# HWProgUSB.net
KiCad netlist of a schematic drawn in EAGLE
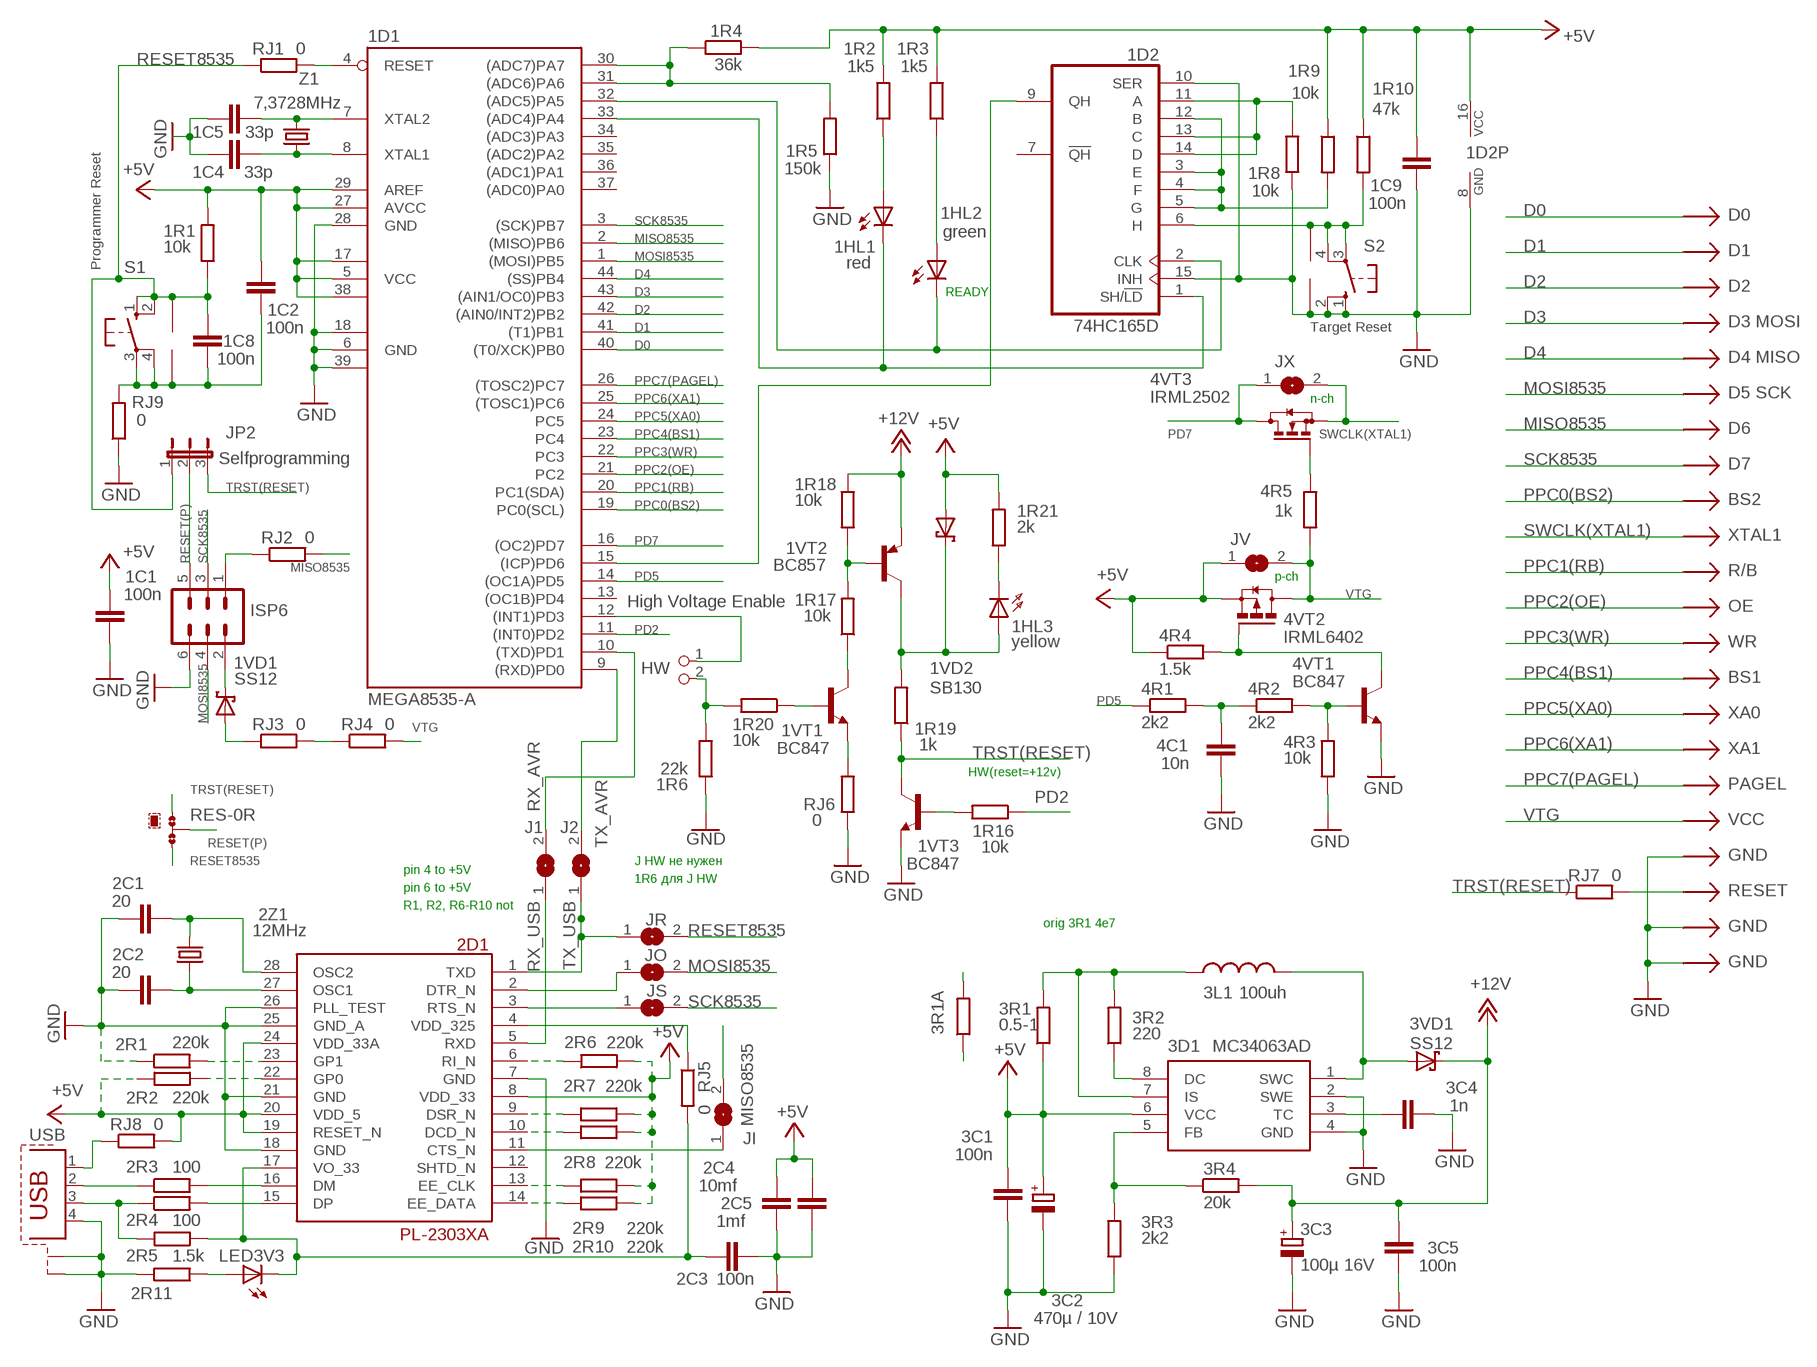
[diagram p0: schematic, sheet 1]

(export (version "E")
  (design (tool "Eeschema 10.0.6"))
  (components
    (comp (ref "1C1")
      (value "100n")
      (footprint "eagle-import:C0805")
      (libsource (lib "eagle-import") (part "rcl_C-EUC0805"))
    )
    (comp (ref "1C2")
      (value "100n")
      (footprint "eagle-import:C0805")
      (libsource (lib "eagle-import") (part "rcl_C-EUC0805"))
    )
    (comp (ref "1C4")
      (value "33p")
      (footprint "eagle-import:C0805")
      (libsource (lib "eagle-import") (part "rcl_C-EUC0805"))
    )
    (comp (ref "1C5")
      (value "33p")
      (footprint "eagle-import:C0805")
      (libsource (lib "eagle-import") (part "rcl_C-EUC0805"))
    )
    (comp (ref "1C8")
      (value "100n")
      (footprint "eagle-import:C0805")
      (libsource (lib "eagle-import") (part "rcl_C-EUC0805"))
    )
    (comp (ref "1C9")
      (value "100n")
      (footprint "eagle-import:C0805")
      (libsource (lib "eagle-import") (part "rcl_C-EUC0805"))
    )
    (comp (ref "1D1")
      (value "MEGA8535-A")
      (footprint "eagle-import:TQFP44")
      (fields (field (name "MPN") "ATMEGA8535-16AU"))
      (libsource (lib "eagle-import") (part "MEGA8535-A"))
    )
    (comp (ref "1D2")
      (value "74HC165D")
      (footprint "eagle-import:SO16")
      (libsource (lib "eagle-import") (part "74165DHC"))
    )
    (comp (ref "1HL1")
      (value "red")
      (footprint "eagle-import:LED5MM")
      (libsource (lib "eagle-import") (part "LED5MM"))
    )
    (comp (ref "1HL2")
      (value "green")
      (footprint "eagle-import:LED5MM")
      (libsource (lib "eagle-import") (part "LED5MM"))
    )
    (comp (ref "1HL3")
      (value "yellow")
      (footprint "eagle-import:LED5MM")
      (libsource (lib "eagle-import") (part "rc-elektronik_LED5MM"))
    )
    (comp (ref "1R1")
      (value "10k")
      (footprint "eagle-import:M0805")
      (libsource (lib "eagle-import") (part "R-EU_M0805"))
    )
    (comp (ref "1R2")
      (value "1k5")
      (footprint "eagle-import:M0805")
      (libsource (lib "eagle-import") (part "R-EU_M0805"))
    )
    (comp (ref "1R3")
      (value "1k5")
      (footprint "eagle-import:M0805")
      (libsource (lib "eagle-import") (part "R-EU_M0805"))
    )
    (comp (ref "1R4")
      (value "36k")
      (footprint "eagle-import:M0805")
      (libsource (lib "eagle-import") (part "R-EU_M0805"))
    )
    (comp (ref "1R5")
      (value "150k")
      (footprint "eagle-import:R1206")
      (libsource (lib "eagle-import") (part "R-EU_R1206"))
    )
    (comp (ref "1R6")
      (value "22k")
      (footprint "eagle-import:M1206")
      (libsource (lib "eagle-import") (part "R-EU_M1206"))
    )
    (comp (ref "1R8")
      (value "10k")
      (footprint "eagle-import:M0805")
      (libsource (lib "eagle-import") (part "R-EU_M0805"))
    )
    (comp (ref "1R9")
      (value "10k")
      (footprint "eagle-import:M0805")
      (libsource (lib "eagle-import") (part "R-EU_M0805"))
    )
    (comp (ref "1R10")
      (value "47k")
      (footprint "eagle-import:M0805")
      (libsource (lib "eagle-import") (part "R-EU_M0805"))
    )
    (comp (ref "1R16")
      (value "10k")
      (footprint "eagle-import:R0805")
      (libsource (lib "eagle-import") (part "R-EU_R0805"))
    )
    (comp (ref "1R17")
      (value "10k")
      (footprint "eagle-import:M0805")
      (libsource (lib "eagle-import") (part "R-EU_M0805"))
    )
    (comp (ref "1R18")
      (value "10k")
      (footprint "eagle-import:M0805")
      (libsource (lib "eagle-import") (part "R-EU_M0805"))
    )
    (comp (ref "1R19")
      (value "1k")
      (footprint "eagle-import:M0805")
      (libsource (lib "eagle-import") (part "R-EU_M0805"))
    )
    (comp (ref "1R20")
      (value "10k")
      (footprint "eagle-import:M0805")
      (libsource (lib "eagle-import") (part "R-EU_M0805"))
    )
    (comp (ref "1R21")
      (value "2k")
      (footprint "eagle-import:R1206W")
      (libsource (lib "eagle-import") (part "R-EU_R1206W"))
    )
    (comp (ref "1VD1")
      (value "SS12")
      (footprint "eagle-import:SMB")
      (libsource (lib "eagle-import") (part "SCHOTTKY-DIODESMD"))
    )
    (comp (ref "1VD2")
      (value "SB130")
      (footprint "eagle-import:SMB")
      (libsource (lib "eagle-import") (part "SCHOTTKY-DIODESMD"))
    )
    (comp (ref "1VT1")
      (value "BC847")
      (footprint "eagle-import:SOT23")
      (libsource (lib "eagle-import") (part "BC847"))
    )
    (comp (ref "1VT2")
      (value "BC857")
      (footprint "eagle-import:SOT23-BEC")
      (libsource (lib "eagle-import") (part "-PNP-SOT23-BECBC857A"))
    )
    (comp (ref "1VT3")
      (value "BC847")
      (footprint "eagle-import:SOT23")
      (libsource (lib "eagle-import") (part "BC847"))
    )
    (comp (ref "2C1")
      (value "20")
      (footprint "eagle-import:C0805")
      (libsource (lib "eagle-import") (part "resistor_C-EUC0805"))
    )
    (comp (ref "2C2")
      (value "20")
      (footprint "eagle-import:C0805")
      (libsource (lib "eagle-import") (part "resistor_C-EUC0805"))
    )
    (comp (ref "2C3")
      (value "100n")
      (footprint "eagle-import:C0805")
      (libsource (lib "eagle-import") (part "resistor_C-EUC0805"))
    )
    (comp (ref "2C4")
      (value "10mf")
      (footprint "eagle-import:C1210")
      (libsource (lib "eagle-import") (part "rcl_C-EUC1210"))
    )
    (comp (ref "2C5")
      (value "1mf")
      (footprint "eagle-import:C0805")
      (libsource (lib "eagle-import") (part "rcl_C-EUC0805"))
    )
    (comp (ref "2D1")
      (value "PL-2303XA")
      (footprint "eagle-import:SSOP28DB")
      (libsource (lib "eagle-import") (part "PL-2303XA"))
    )
    (comp (ref "2R1")
      (value "220k")
      (footprint "eagle-import:R0603")
      (libsource (lib "eagle-import") (part "resistor_R-EU_R0603"))
    )
    (comp (ref "2R2")
      (value "220k")
      (footprint "eagle-import:R1206W")
      (libsource (lib "eagle-import") (part "resistor_R-EU_R1206W"))
    )
    (comp (ref "2R3")
      (value "100")
      (footprint "eagle-import:R0603")
      (libsource (lib "eagle-import") (part "resistor_R-EU_R0603"))
    )
    (comp (ref "2R4")
      (value "100")
      (footprint "eagle-import:R0603")
      (libsource (lib "eagle-import") (part "resistor_R-EU_R0603"))
    )
    (comp (ref "2R5")
      (value "1.5k")
      (footprint "eagle-import:R0603")
      (libsource (lib "eagle-import") (part "resistor_R-EU_R0603"))
    )
    (comp (ref "2R6")
      (value "220k")
      (footprint "eagle-import:R1206W")
      (libsource (lib "eagle-import") (part "resistor_R-EU_R1206W"))
    )
    (comp (ref "2R7")
      (value "220k")
      (footprint "eagle-import:R0603")
      (libsource (lib "eagle-import") (part "resistor_R-EU_R0603"))
    )
    (comp (ref "2R8")
      (value "220k")
      (footprint "eagle-import:R0603")
      (libsource (lib "eagle-import") (part "resistor_R-EU_R0603"))
    )
    (comp (ref "2R9")
      (value "220k")
      (footprint "eagle-import:R0603")
      (libsource (lib "eagle-import") (part "resistor_R-EU_R0603"))
    )
    (comp (ref "2R10")
      (value "220k")
      (footprint "eagle-import:R0603")
      (libsource (lib "eagle-import") (part "resistor_R-EU_R0603"))
    )
    (comp (ref "2R11")
      (value "R-EU_R0603")
      (footprint "eagle-import:R0603")
      (libsource (lib "eagle-import") (part "resistor_R-EU_R0603"))
    )
    (comp (ref "2Z1")
      (value "12MHz")
      (footprint "eagle-import:HC49_S")
      (libsource (lib "eagle-import") (part "CRYSTALHC49S"))
    )
    (comp (ref "3C1")
      (value "100n")
      (footprint "eagle-import:C025-024X044")
      (libsource (lib "eagle-import") (part "C-EU025-024X044"))
    )
    (comp (ref "3C2")
      (value "470µ / 10V")
      (footprint "eagle-import:RCL_E3,5-8")
      (libsource (lib "eagle-import") (part "RCL_CPOL-EUE3.5-8"))
    )
    (comp (ref "3C3")
      (value "100µ 16V")
      (footprint "eagle-import:RCL_E3,5-8")
      (libsource (lib "eagle-import") (part "RCL_CPOL-EUE3.5-8"))
    )
    (comp (ref "3C4")
      (value "1n")
      (footprint "eagle-import:C025-025X050")
      (libsource (lib "eagle-import") (part "rcl_C-EU025-025X050"))
    )
    (comp (ref "3C5")
      (value "100n")
      (footprint "eagle-import:C025-025X050")
      (libsource (lib "eagle-import") (part "rcl_C-EU025-025X050"))
    )
    (comp (ref "3D1")
      (value "MC34063AD")
      (footprint "eagle-import:SOIC8")
      (libsource (lib "eagle-import") (part "MC34063AD"))
    )
    (comp (ref "3L1")
      (value "100uh")
      (footprint "eagle-import:0207_10")
      (libsource (lib "eagle-import") (part "L-US0207/10"))
    )
    (comp (ref "3R1")
      (value "0.5-1")
      (footprint "eagle-import:0204_7")
      (libsource (lib "eagle-import") (part "R-EU_0204/7"))
    )
    (comp (ref "3R1A")
      (value "R-EU_0204/7")
      (footprint "eagle-import:0204_7")
      (libsource (lib "eagle-import") (part "R-EU_0204/7"))
    )
    (comp (ref "3R2")
      (value "220")
      (footprint "eagle-import:0204_7")
      (libsource (lib "eagle-import") (part "R-EU_0204/7"))
    )
    (comp (ref "3R3")
      (value "2k2")
      (footprint "eagle-import:M0805")
      (libsource (lib "eagle-import") (part "R-EU_M0805"))
    )
    (comp (ref "3R4")
      (value "20k")
      (footprint "eagle-import:M0805")
      (libsource (lib "eagle-import") (part "R-EU_M0805"))
    )
    (comp (ref "3VD1")
      (value "SS12")
      (footprint "eagle-import:SMB")
      (libsource (lib "eagle-import") (part "SCHOTTKY-DIODESMD"))
    )
    (comp (ref "4C1")
      (value "10n")
      (footprint "eagle-import:C1206")
      (libsource (lib "eagle-import") (part "rcl_C-EUC1206"))
    )
    (comp (ref "4R1")
      (value "2k2")
      (footprint "eagle-import:M0805")
      (libsource (lib "eagle-import") (part "R-EU_M0805"))
    )
    (comp (ref "4R2")
      (value "2k2")
      (footprint "eagle-import:M1206")
      (libsource (lib "eagle-import") (part "R-EU_M1206"))
    )
    (comp (ref "4R3")
      (value "10k")
      (footprint "eagle-import:M0805")
      (libsource (lib "eagle-import") (part "R-EU_M0805"))
    )
    (comp (ref "4R4")
      (value "1.5k")
      (footprint "eagle-import:M0805")
      (libsource (lib "eagle-import") (part "R-EU_M0805"))
    )
    (comp (ref "4R5")
      (value "1k")
      (footprint "eagle-import:M0805")
      (libsource (lib "eagle-import") (part "R-EU_M0805"))
    )
    (comp (ref "4VT1")
      (value "BC847")
      (footprint "eagle-import:SOT23")
      (libsource (lib "eagle-import") (part "transistor-neu-to92_BC847"))
    )
    (comp (ref "4VT2")
      (value "IRML6402")
      (footprint "eagle-import:SUPER-SOT3")
      (libsource (lib "eagle-import") (part "FDN360P"))
    )
    (comp (ref "4VT3")
      (value "IRML2502")
      (footprint "eagle-import:SOT23")
      (libsource (lib "eagle-import") (part "BSS123"))
    )
    (comp (ref "HW")
      (value "High Voltage Enable")
      (footprint "eagle-import:PINHEAD_1X02")
      (libsource (lib "eagle-import") (part "PINHEAD_PINHD-1X2"))
    )
    (comp (ref "ISP6")
      (value "MA03-2")
      (footprint "eagle-import:MA03-2")
      (libsource (lib "eagle-import") (part "MA03-2"))
    )
    (comp (ref "J1") (value "SJ") (footprint "eagle-import:SJ") (libsource (lib "eagle-import") (part "SJ")))
    (comp (ref "J2") (value "SJ") (footprint "eagle-import:SJ") (libsource (lib "eagle-import") (part "SJ")))
    (comp (ref "JI") (value "SJ") (footprint "eagle-import:SJ") (libsource (lib "eagle-import") (part "SJ")))
    (comp (ref "JO") (value "SJ") (footprint "eagle-import:SJ") (libsource (lib "eagle-import") (part "SJ")))
    (comp (ref "JP2")
      (value "Selfprogramming")
      (footprint "eagle-import:JUMPER_JP2")
      (libsource (lib "eagle-import") (part "JUMPER_JP2E"))
    )
    (comp (ref "JR") (value "SJ") (footprint "eagle-import:SJ") (libsource (lib "eagle-import") (part "SJ")))
    (comp (ref "JS") (value "SJ") (footprint "eagle-import:SJ") (libsource (lib "eagle-import") (part "SJ")))
    (comp (ref "JV") (value "SJ") (footprint "eagle-import:SJ") (libsource (lib "eagle-import") (part "SJ")))
    (comp (ref "JX") (value "SJ") (footprint "eagle-import:SJ") (libsource (lib "eagle-import") (part "SJ")))
    (comp (ref "LED3V3")
      (value "LEDCHIPLED_0603")
      (footprint "eagle-import:CHIPLED_0603")
      (libsource (lib "eagle-import") (part "LEDCHIPLED_0603"))
    )
    (comp (ref "RES")
      (value "0R-JUMPA")
      (footprint "eagle-import:A0R-JMP")
      (libsource (lib "eagle-import") (part "0R-JUMPA"))
    )
    (comp (ref "RJ1")
      (value "0")
      (footprint "eagle-import:R1206")
      (libsource (lib "eagle-import") (part "R-EU_R1206"))
    )
    (comp (ref "RJ2")
      (value "0")
      (footprint "eagle-import:R1206")
      (libsource (lib "eagle-import") (part "R-EU_R1206"))
    )
    (comp (ref "RJ3")
      (value "0")
      (footprint "eagle-import:R1206")
      (libsource (lib "eagle-import") (part "R-EU_R1206"))
    )
    (comp (ref "RJ4")
      (value "0")
      (footprint "eagle-import:R1206")
      (libsource (lib "eagle-import") (part "R-EU_R1206"))
    )
    (comp (ref "RJ5")
      (value "0")
      (footprint "eagle-import:R1206")
      (libsource (lib "eagle-import") (part "R-EU_R1206"))
    )
    (comp (ref "RJ6")
      (value "0")
      (footprint "eagle-import:R1206")
      (libsource (lib "eagle-import") (part "R-EU_R1206"))
    )
    (comp (ref "RJ7")
      (value "0")
      (footprint "eagle-import:R1206")
      (libsource (lib "eagle-import") (part "R-EU_R1206"))
    )
    (comp (ref "RJ8")
      (value "0")
      (footprint "eagle-import:R1206")
      (libsource (lib "eagle-import") (part "R-EU_R1206"))
    )
    (comp (ref "RJ9")
      (value "0")
      (footprint "eagle-import:R1206")
      (libsource (lib "eagle-import") (part "R-EU_R1206"))
    )
    (comp (ref "S1")
      (value "10-XX")
      (footprint "eagle-import:B3F-10XX")
      (libsource (lib "eagle-import") (part "10-XX"))
    )
    (comp (ref "S2")
      (value "10-XX")
      (footprint "eagle-import:B3F-10XX")
      (libsource (lib "eagle-import") (part "10-XX"))
    )
    (comp (ref "U$1")
      (value "5.08")
      (footprint "eagle-import:KEY")
      (libsource (lib "eagle-import") (part "5.08"))
    )
    (comp (ref "U$2")
      (value "5.08")
      (footprint "eagle-import:KEY")
      (libsource (lib "eagle-import") (part "5.08"))
    )
    (comp (ref "USB")
      (value "PROGRAMMER_PN61729-S")
      (footprint "eagle-import:PROGRAMMER_PN61729-S")
      (libsource (lib "eagle-import") (part "PROGRAMMER_PN61729-S"))
    )
    (comp (ref "X2")
      (value "P_AVR_P")
      (footprint "eagle-import:P_AVR")
      (libsource (lib "eagle-import") (part "P_AVR_P"))
    )
    (comp (ref "Z1")
      (value "7,3728MHz")
      (footprint "eagle-import:HC49U-V")
      (libsource (lib "eagle-import") (part "CRYTALHC49U-V"))
    )
  )
  (nets
    (net (code "1") (name "+5V") (class "Default")
      (node (ref "1C1") (pin "2") (pinfunction "2_2") (pintype "passive"))
      (node (ref "1C2") (pin "2") (pinfunction "2_2") (pintype "passive"))
      (node (ref "1C9") (pin "1") (pinfunction "1_1") (pintype "passive"))
      (node (ref "1D1") (pin "17") (pinfunction "VCC1_17") (pintype "power_in"))
      (node (ref "1D1") (pin "27") (pinfunction "AVCC_27") (pintype "power_in"))
      (node (ref "1D1") (pin "29") (pinfunction "AREF_29") (pintype "passive"))
      (node (ref "1D1") (pin "38") (pinfunction "VCC2_38") (pintype "power_in"))
      (node (ref "1D1") (pin "5") (pinfunction "VCC_5") (pintype "power_in"))
      (node (ref "1D2") (pin "16") (pinfunction "VCC_16") (pintype "power_in"))
      (node (ref "1R1") (pin "2") (pinfunction "2_2") (pintype "passive"))
      (node (ref "1R10") (pin "1") (pinfunction "1_1") (pintype "passive"))
      (node (ref "1R2") (pin "2") (pinfunction "2_2") (pintype "passive"))
      (node (ref "1R21") (pin "2") (pinfunction "2_2") (pintype "passive"))
      (node (ref "1R3") (pin "2") (pinfunction "2_2") (pintype "passive"))
      (node (ref "1R4") (pin "2") (pinfunction "2_2") (pintype "passive"))
      (node (ref "1R9") (pin "1") (pinfunction "1_1") (pintype "passive"))
      (node (ref "1VD2") (pin "A") (pinfunction "A_A") (pintype "passive"))
      (node (ref "2C4") (pin "2") (pinfunction "2_2") (pintype "passive"))
      (node (ref "2C5") (pin "2") (pinfunction "2_2") (pintype "passive"))
      (node (ref "2D1") (pin "19") (pinfunction "RESET_N_19") (pintype "bidirectional"))
      (node (ref "2D1") (pin "20") (pinfunction "VDD_5_20") (pintype "bidirectional"))
      (node (ref "2D1") (pin "24") (pinfunction "VDD_33A_24") (pintype "bidirectional"))
      (node (ref "2D1") (pin "8") (pinfunction "VDD_33_8") (pintype "bidirectional"))
      (node (ref "2R10") (pin "1") (pinfunction "1_1") (pintype "passive"))
      (node (ref "2R2") (pin "1") (pinfunction "1_1") (pintype "passive"))
      (node (ref "2R6") (pin "2") (pinfunction "2_2") (pintype "passive"))
      (node (ref "2R7") (pin "1") (pinfunction "1_1") (pintype "passive"))
      (node (ref "2R8") (pin "1") (pinfunction "1_1") (pintype "passive"))
      (node (ref "2R9") (pin "1") (pinfunction "1_1") (pintype "passive"))
      (node (ref "3C1") (pin "1") (pinfunction "1_1") (pintype "passive"))
      (node (ref "3C2") (pin "+") (pinfunction "+_+") (pintype "passive"))
      (node (ref "3D1") (pin "6") (pinfunction "VCC_6") (pintype "passive"))
      (node (ref "3R1") (pin "1") (pinfunction "1_1") (pintype "passive"))
      (node (ref "3R1A") (pin "1") (pinfunction "1_1") (pintype "passive"))
      (node (ref "4R4") (pin "1") (pinfunction "1_1") (pintype "passive"))
      (node (ref "4VT2") (pin "2") (pinfunction "S_2") (pintype "passive"))
      (node (ref "JV") (pin "1") (pinfunction "1_1") (pintype "passive"))
      (node (ref "RJ8") (pin "2") (pinfunction "2_2") (pintype "passive"))
    )
    (net (code "2") (name "+12V") (class "Default")
      (node (ref "1R18") (pin "2") (pinfunction "2_2") (pintype "passive"))
      (node (ref "1VT2") (pin "E") (pinfunction "E_E") (pintype "passive"))
      (node (ref "3C3") (pin "+") (pinfunction "+_+") (pintype "passive"))
      (node (ref "3C5") (pin "2") (pinfunction "2_2") (pintype "passive"))
      (node (ref "3R4") (pin "2") (pinfunction "2_2") (pintype "passive"))
      (node (ref "3VD1") (pin "C") (pinfunction "C_C") (pintype "passive"))
    )
    (net (code "3") (name "/D0") (class "Default")
      (node (ref "1D1") (pin "40") (pinfunction "(T0/XCK)PB0_40") (pintype "bidirectional"))
      (node (ref "X2") (pin "D0") (pinfunction "D0_D0") (pintype "bidirectional"))
    )
    (net (code "4") (name "/D1") (class "Default")
      (node (ref "1D1") (pin "41") (pinfunction "(T1)PB1_41") (pintype "bidirectional"))
      (node (ref "X2") (pin "D1") (pinfunction "D1_D1") (pintype "bidirectional"))
    )
    (net (code "5") (name "/D2") (class "Default")
      (node (ref "1D1") (pin "42") (pinfunction "(AIN0/INT2)PB2_42") (pintype "bidirectional"))
      (node (ref "X2") (pin "D2") (pinfunction "D2_D2") (pintype "bidirectional"))
    )
    (net (code "6") (name "/D3") (class "Default")
      (node (ref "1D1") (pin "43") (pinfunction "(AIN1/OC0)PB3_43") (pintype "bidirectional"))
      (node (ref "X2") (pin "D3") (pinfunction "D3_D3") (pintype "bidirectional"))
    )
    (net (code "7") (name "/D4") (class "Default")
      (node (ref "1D1") (pin "44") (pinfunction "(SS)PB4_44") (pintype "bidirectional"))
      (node (ref "X2") (pin "D4") (pinfunction "D4_D4") (pintype "bidirectional"))
    )
    (net (code "8") (name "/MISO8535") (class "Default")
      (node (ref "1D1") (pin "2") (pinfunction "(MISO)PB6_2") (pintype "bidirectional"))
      (node (ref "JI") (pin "2") (pinfunction "2_2") (pintype "passive"))
      (node (ref "RJ2") (pin "2") (pinfunction "2_2") (pintype "passive"))
      (node (ref "X2") (pin "D6") (pinfunction "D6_D6") (pintype "bidirectional"))
    )
    (net (code "9") (name "/MOSI8535") (class "Default")
      (node (ref "1D1") (pin "1") (pinfunction "(MOSI)PB5_1") (pintype "bidirectional"))
      (node (ref "ISP6") (pin "4") (pinfunction "4_4") (pintype "passive"))
      (node (ref "JO") (pin "2") (pinfunction "2_2") (pintype "passive"))
      (node (ref "X2") (pin "D5") (pinfunction "D5_D5") (pintype "bidirectional"))
    )
    (net (code "10") (name "/N$105") (class "Default")
      (node (ref "3D1") (pin "7") (pinfunction "IS_7") (pintype "passive"))
      (node (ref "3L1") (pin "1") (pinfunction "1_1") (pintype "passive"))
      (node (ref "3R1") (pin "2") (pinfunction "2_2") (pintype "passive"))
      (node (ref "3R1A") (pin "2") (pinfunction "2_2") (pintype "passive"))
      (node (ref "3R2") (pin "2") (pinfunction "2_2") (pintype "passive"))
    )
    (net (code "11") (name "/PD2") (class "Default")
      (node (ref "1D1") (pin "11") (pinfunction "(INT0)PD2_11") (pintype "bidirectional"))
      (node (ref "1R16") (pin "1") (pinfunction "1_1") (pintype "passive"))
    )
    (net (code "12") (name "/PD5") (class "Default")
      (node (ref "1D1") (pin "14") (pinfunction "(OC1A)PD5_14") (pintype "bidirectional"))
      (node (ref "4R1") (pin "1") (pinfunction "1_1") (pintype "passive"))
    )
    (net (code "13") (name "/PD7") (class "Default")
      (node (ref "1D1") (pin "16") (pinfunction "(OC2)PD7_16") (pintype "bidirectional"))
      (node (ref "4VT3") (pin "3") (pinfunction "D_3") (pintype "passive"))
      (node (ref "JX") (pin "1") (pinfunction "1_1") (pintype "passive"))
    )
    (net (code "14") (name "/PPC0(BS2)") (class "Default")
      (node (ref "1D1") (pin "19") (pinfunction "PC0(SCL)_19") (pintype "bidirectional"))
      (node (ref "X2") (pin "BS2") (pinfunction "BS2_BS2") (pintype "bidirectional"))
    )
    (net (code "15") (name "/PPC1(RB)") (class "Default")
      (node (ref "1D1") (pin "20") (pinfunction "PC1(SDA)_20") (pintype "bidirectional"))
      (node (ref "X2") (pin "RB") (pinfunction "RB_RB") (pintype "bidirectional"))
    )
    (net (code "16") (name "/PPC2(OE)") (class "Default")
      (node (ref "1D1") (pin "21") (pinfunction "PC2_21") (pintype "bidirectional"))
      (node (ref "X2") (pin "OE") (pinfunction "OE_OE") (pintype "bidirectional"))
    )
    (net (code "17") (name "/PPC3(WR)") (class "Default")
      (node (ref "1D1") (pin "22") (pinfunction "PC3_22") (pintype "bidirectional"))
      (node (ref "X2") (pin "WR") (pinfunction "WR_WR") (pintype "bidirectional"))
    )
    (net (code "18") (name "/PPC4(BS1)") (class "Default")
      (node (ref "1D1") (pin "23") (pinfunction "PC4_23") (pintype "bidirectional"))
      (node (ref "X2") (pin "BS1") (pinfunction "BS1_BS1") (pintype "bidirectional"))
    )
    (net (code "19") (name "/PPC5(XA0)") (class "Default")
      (node (ref "1D1") (pin "24") (pinfunction "PC5_24") (pintype "bidirectional"))
      (node (ref "X2") (pin "XA0") (pinfunction "XA0_XA0") (pintype "bidirectional"))
    )
    (net (code "20") (name "/PPC6(XA1)") (class "Default")
      (node (ref "1D1") (pin "25") (pinfunction "(TOSC1)PC6_25") (pintype "bidirectional"))
      (node (ref "X2") (pin "XA1") (pinfunction "XA1_XA1") (pintype "bidirectional"))
    )
    (net (code "21") (name "/PPC7(PAGEL)") (class "Default")
      (node (ref "1D1") (pin "26") (pinfunction "(TOSC2)PC7_26") (pintype "bidirectional"))
      (node (ref "X2") (pin "PAGEL") (pinfunction "PAGEL_PAGEL") (pintype "bidirectional"))
    )
    (net (code "22") (name "/RESET(P)") (class "Default")
      (node (ref "ISP6") (pin "5") (pinfunction "5_5") (pintype "passive"))
      (node (ref "JP2") (pin "2") (pinfunction "2_2") (pintype "passive"))
      (node (ref "RES") (pin "2") (pinfunction "2_2") (pintype "passive"))
    )
    (net (code "23") (name "/RESET8535") (class "Default")
      (node (ref "1C8") (pin "2") (pinfunction "2_2") (pintype "passive"))
      (node (ref "1R1") (pin "1") (pinfunction "1_1") (pintype "passive"))
      (node (ref "JP2") (pin "1") (pinfunction "1_1") (pintype "passive"))
      (node (ref "JR") (pin "2") (pinfunction "2_2") (pintype "passive"))
      (node (ref "RES") (pin "3") (pinfunction "3_3") (pintype "passive"))
      (node (ref "RJ1") (pin "1") (pinfunction "1_1") (pintype "passive"))
      (node (ref "S1") (pin "1") (pinfunction "S_1") (pintype "passive"))
      (node (ref "S1") (pin "2") (pinfunction "S1_2") (pintype "passive"))
      (node (ref "U$1") (pin "P$2") (pinfunction "P$2_P$2") (pintype "bidirectional"))
    )
    (net (code "24") (name "/RX_AVR") (class "Default")
      (node (ref "1D1") (pin "10") (pinfunction "(TXD)PD1_10") (pintype "bidirectional"))
      (node (ref "J1") (pin "2") (pinfunction "2_2") (pintype "passive"))
    )
    (net (code "25") (name "/RX_USB") (class "Default")
      (node (ref "2D1") (pin "5") (pinfunction "RXD_5") (pintype "bidirectional"))
      (node (ref "J1") (pin "1") (pinfunction "1_1") (pintype "passive"))
    )
    (net (code "26") (name "/SCK8535") (class "Default")
      (node (ref "1D1") (pin "3") (pinfunction "(SCK)PB7_3") (pintype "bidirectional"))
      (node (ref "ISP6") (pin "3") (pinfunction "3_3") (pintype "passive"))
      (node (ref "JS") (pin "2") (pinfunction "2_2") (pintype "passive"))
      (node (ref "X2") (pin "D7") (pinfunction "D7_D7") (pintype "bidirectional"))
    )
    (net (code "27") (name "/SWCLK(XTAL1)") (class "Default")
      (node (ref "4VT3") (pin "2") (pinfunction "S_2") (pintype "passive"))
      (node (ref "JX") (pin "2") (pinfunction "2_2") (pintype "passive"))
      (node (ref "X2") (pin "XTAL1") (pinfunction "XTAL1_XTAL1") (pintype "bidirectional"))
    )
    (net (code "28") (name "/TRST(RESET)") (class "Default")
      (node (ref "1R19") (pin "1") (pinfunction "1_1") (pintype "passive"))
      (node (ref "1VT3") (pin "3") (pinfunction "C_3") (pintype "passive"))
      (node (ref "JP2") (pin "3") (pinfunction "3_3") (pintype "passive"))
      (node (ref "RES") (pin "1") (pinfunction "1_1") (pintype "passive"))
      (node (ref "RJ7") (pin "1") (pinfunction "1_1") (pintype "passive"))
    )
    (net (code "29") (name "/TX_AVR") (class "Default")
      (node (ref "1D1") (pin "9") (pinfunction "(RXD)PD0_9") (pintype "bidirectional"))
      (node (ref "J2") (pin "2") (pinfunction "2_2") (pintype "passive"))
    )
    (net (code "30") (name "/TX_USB") (class "Default")
      (node (ref "2D1") (pin "1") (pinfunction "TXD_1") (pintype "bidirectional"))
      (node (ref "J2") (pin "1") (pinfunction "1_1") (pintype "passive"))
      (node (ref "JR") (pin "1") (pinfunction "1_1") (pintype "passive"))
    )
    (net (code "31") (name "/VTG") (class "Default")
      (node (ref "4R5") (pin "1") (pinfunction "1_1") (pintype "passive"))
      (node (ref "4VT2") (pin "3") (pinfunction "D_3") (pintype "passive"))
      (node (ref "JV") (pin "2") (pinfunction "2_2") (pintype "passive"))
      (node (ref "RJ4") (pin "2") (pinfunction "2_2") (pintype "passive"))
      (node (ref "X2") (pin "VCC") (pinfunction "VCC_VCC") (pintype "bidirectional"))
    )
    (net (code "32") (name "GND") (class "Default")
      (node (ref "1C1") (pin "1") (pinfunction "1_1") (pintype "passive"))
      (node (ref "1C4") (pin "1") (pinfunction "1_1") (pintype "passive"))
      (node (ref "1C5") (pin "1") (pinfunction "1_1") (pintype "passive"))
      (node (ref "1C9") (pin "2") (pinfunction "2_2") (pintype "passive"))
      (node (ref "1D1") (pin "18") (pinfunction "GND1_18") (pintype "power_in"))
      (node (ref "1D1") (pin "28") (pinfunction "GND_28") (pintype "power_in"))
      (node (ref "1D1") (pin "39") (pinfunction "GND2_39") (pintype "power_in"))
      (node (ref "1D1") (pin "6") (pinfunction "GND_6") (pintype "power_in"))
      (node (ref "1D2") (pin "10") (pinfunction "SER_10") (pintype "input"))
      (node (ref "1D2") (pin "15") (pinfunction "INH_15") (pintype "input"))
      (node (ref "1D2") (pin "8") (pinfunction "GND_8") (pintype "power_in"))
      (node (ref "1R5") (pin "1") (pinfunction "1_1") (pintype "passive"))
      (node (ref "1R6") (pin "1") (pinfunction "1_1") (pintype "passive"))
      (node (ref "1R8") (pin "1") (pinfunction "1_1") (pintype "passive"))
      (node (ref "1VT3") (pin "2") (pinfunction "E_2") (pintype "passive"))
      (node (ref "2C1") (pin "1") (pinfunction "1_1") (pintype "passive"))
      (node (ref "2C2") (pin "1") (pinfunction "1_1") (pintype "passive"))
      (node (ref "2C3") (pin "2") (pinfunction "2_2") (pintype "passive"))
      (node (ref "2C4") (pin "1") (pinfunction "1_1") (pintype "passive"))
      (node (ref "2C5") (pin "1") (pinfunction "1_1") (pintype "passive"))
      (node (ref "2D1") (pin "18") (pinfunction "GND_18") (pintype "bidirectional"))
      (node (ref "2D1") (pin "21") (pinfunction "GND_21") (pintype "bidirectional"))
      (node (ref "2D1") (pin "25") (pinfunction "GND_A_25") (pintype "bidirectional"))
      (node (ref "2D1") (pin "26") (pinfunction "PLL_TEST_26") (pintype "bidirectional"))
      (node (ref "2D1") (pin "7") (pinfunction "GND_7") (pintype "bidirectional"))
      (node (ref "2R1") (pin "1") (pinfunction "1_1") (pintype "passive"))
      (node (ref "2R11") (pin "2") (pinfunction "2_2") (pintype "passive"))
      (node (ref "3C1") (pin "2") (pinfunction "2_2") (pintype "passive"))
      (node (ref "3C2") (pin "-") (pinfunction "-_-") (pintype "passive"))
      (node (ref "3C3") (pin "-") (pinfunction "-_-") (pintype "passive"))
      (node (ref "3C4") (pin "2") (pinfunction "2_2") (pintype "passive"))
      (node (ref "3C5") (pin "1") (pinfunction "1_1") (pintype "passive"))
      (node (ref "3D1") (pin "2") (pinfunction "SWE_2") (pintype "passive"))
      (node (ref "3D1") (pin "4") (pinfunction "GND_4") (pintype "passive"))
      (node (ref "3R3") (pin "1") (pinfunction "1_1") (pintype "passive"))
      (node (ref "4C1") (pin "1") (pinfunction "1_1") (pintype "passive"))
      (node (ref "4R3") (pin "1") (pinfunction "1_1") (pintype "passive"))
      (node (ref "4VT1") (pin "2") (pinfunction "E_2") (pintype "passive"))
      (node (ref "ISP6") (pin "6") (pinfunction "6_6") (pintype "passive"))
      (node (ref "RJ6") (pin "1") (pinfunction "1_1") (pintype "passive"))
      (node (ref "RJ9") (pin "1") (pinfunction "1_1") (pintype "passive"))
      (node (ref "S2") (pin "1") (pinfunction "S_1") (pintype "passive"))
      (node (ref "S2") (pin "2") (pinfunction "S1_2") (pintype "passive"))
      (node (ref "U$2") (pin "P$1") (pinfunction "P$1_P$1") (pintype "bidirectional"))
      (node (ref "USB") (pin "4") (pinfunction "4_4") (pintype "passive"))
      (node (ref "USB") (pin "S1") (pinfunction "S1_S1") (pintype "passive"))
      (node (ref "USB") (pin "S2") (pinfunction "S2_S2") (pintype "passive"))
      (node (ref "X2") (pin "GND") (pinfunction "GND_GND") (pintype "bidirectional"))
      (node (ref "X2") (pin "GND2") (pinfunction "GND2_GND2") (pintype "bidirectional"))
      (node (ref "X2") (pin "P$1") (pinfunction "LGND_P$1") (pintype "bidirectional"))
    )
    (net (code "33") (name "Net-(1D1-(ADC4)PA4)") (class "Default")
      (node (ref "1D1") (pin "33") (pinfunction "(ADC4)PA4_33") (pintype "bidirectional"))
      (node (ref "1D2") (pin "1") (pinfunction "SH/~{LD}_1") (pintype "input"))
      (node (ref "1HL1") (pin "K") (pinfunction "C_K") (pintype "passive"))
    )
    (net (code "34") (name "Net-(1D1-(ADC5)PA5)") (class "Default")
      (node (ref "1D1") (pin "32") (pinfunction "(ADC5)PA5_32") (pintype "bidirectional"))
      (node (ref "1D2") (pin "2") (pinfunction "CLK_2") (pintype "input"))
      (node (ref "1HL2") (pin "K") (pinfunction "C_K") (pintype "passive"))
    )
    (net (code "35") (name "Net-(1D1-(ADC6)PA6)") (class "Default")
      (node (ref "1D1") (pin "30") (pinfunction "(ADC7)PA7_30") (pintype "bidirectional"))
      (node (ref "1D1") (pin "31") (pinfunction "(ADC6)PA6_31") (pintype "bidirectional"))
      (node (ref "1R4") (pin "1") (pinfunction "1_1") (pintype "passive"))
      (node (ref "1R5") (pin "2") (pinfunction "2_2") (pintype "passive"))
    )
    (net (code "36") (name "Net-(1D1-(ICP)PD6)") (class "Default")
      (node (ref "1D1") (pin "15") (pinfunction "(ICP)PD6_15") (pintype "bidirectional"))
      (node (ref "1D2") (pin "9") (pinfunction "QH_9") (pintype "output"))
    )
    (net (code "37") (name "Net-(1D1-(INT1)PD3)") (class "Default")
      (node (ref "1D1") (pin "12") (pinfunction "(INT1)PD3_12") (pintype "bidirectional"))
      (node (ref "HW") (pin "1") (pinfunction "1_1") (pintype "passive"))
    )
    (net (code "38") (name "Net-(1D1-RESET)") (class "Default")
      (node (ref "1D1") (pin "4") (pinfunction "RESET_4") (pintype "input"))
      (node (ref "RJ1") (pin "2") (pinfunction "2_2") (pintype "passive"))
    )
    (net (code "39") (name "Net-(1D1-XTAL1)") (class "Default")
      (node (ref "1C4") (pin "2") (pinfunction "2_2") (pintype "passive"))
      (node (ref "1D1") (pin "8") (pinfunction "XTAL1_8") (pintype "bidirectional"))
      (node (ref "Z1") (pin "1") (pinfunction "1_1") (pintype "passive"))
    )
    (net (code "40") (name "Net-(1D1-XTAL2)") (class "Default")
      (node (ref "1C5") (pin "2") (pinfunction "2_2") (pintype "passive"))
      (node (ref "1D1") (pin "7") (pinfunction "XTAL2_7") (pintype "bidirectional"))
      (node (ref "Z1") (pin "2") (pinfunction "2_2") (pintype "passive"))
    )
    (net (code "41") (name "Net-(1D2A-A)") (class "Default")
      (node (ref "1D2") (pin "11") (pinfunction "A_11") (pintype "input"))
      (node (ref "1D2") (pin "13") (pinfunction "C_13") (pintype "input"))
      (node (ref "1D2") (pin "14") (pinfunction "D_14") (pintype "input"))
      (node (ref "1R8") (pin "2") (pinfunction "2_2") (pintype "passive"))
    )
    (net (code "42") (name "Net-(1D2A-B)") (class "Default")
      (node (ref "1D2") (pin "12") (pinfunction "B_12") (pintype "input"))
      (node (ref "1D2") (pin "3") (pinfunction "E_3") (pintype "input"))
      (node (ref "1D2") (pin "4") (pinfunction "F_4") (pintype "input"))
      (node (ref "1D2") (pin "5") (pinfunction "G_5") (pintype "input"))
      (node (ref "1R9") (pin "2") (pinfunction "2_2") (pintype "passive"))
    )
    (net (code "43") (name "Net-(1D2A-H)") (class "Default")
      (node (ref "1D2") (pin "6") (pinfunction "H_6") (pintype "input"))
      (node (ref "1R10") (pin "2") (pinfunction "2_2") (pintype "passive"))
      (node (ref "S2") (pin "3") (pinfunction "P_3") (pintype "passive"))
      (node (ref "S2") (pin "4") (pinfunction "P1_4") (pintype "passive"))
      (node (ref "U$2") (pin "P$2") (pinfunction "P$2_P$2") (pintype "bidirectional"))
    )
    (net (code "44") (name "Net-(1HL1-PadA)") (class "Default")
      (node (ref "1HL1") (pin "A") (pinfunction "A_A") (pintype "passive"))
      (node (ref "1R2") (pin "1") (pinfunction "1_1") (pintype "passive"))
    )
    (net (code "45") (name "Net-(1HL2-PadA)") (class "Default")
      (node (ref "1HL2") (pin "A") (pinfunction "A_A") (pintype "passive"))
      (node (ref "1R3") (pin "1") (pinfunction "1_1") (pintype "passive"))
    )
    (net (code "46") (name "Net-(1HL3-C)") (class "Default")
      (node (ref "1HL3") (pin "K") (pinfunction "C_K") (pintype "passive"))
      (node (ref "1R21") (pin "1") (pinfunction "1_1") (pintype "passive"))
    )
    (net (code "47") (name "Net-(1HL3-PadA)") (class "Default")
      (node (ref "1HL3") (pin "A") (pinfunction "A_A") (pintype "passive"))
      (node (ref "1R19") (pin "2") (pinfunction "2_2") (pintype "passive"))
      (node (ref "1VD2") (pin "C") (pinfunction "C_C") (pintype "passive"))
      (node (ref "1VT2") (pin "C") (pinfunction "C_C") (pintype "passive"))
    )
    (net (code "48") (name "Net-(1R17-Pad2)") (class "Default")
      (node (ref "1R17") (pin "2") (pinfunction "2_2") (pintype "passive"))
      (node (ref "1R18") (pin "1") (pinfunction "1_1") (pintype "passive"))
      (node (ref "1VT2") (pin "B") (pinfunction "B_B") (pintype "passive"))
    )
    (net (code "49") (name "Net-(1R20-Pad2)") (class "Default")
      (node (ref "1R20") (pin "2") (pinfunction "2_2") (pintype "passive"))
      (node (ref "1R6") (pin "2") (pinfunction "2_2") (pintype "passive"))
      (node (ref "HW") (pin "2") (pinfunction "2_2") (pintype "passive"))
    )
    (net (code "50") (name "Net-(1VD1-PadA)") (class "Default")
      (node (ref "1VD1") (pin "A") (pinfunction "A_A") (pintype "passive"))
      (node (ref "RJ3") (pin "1") (pinfunction "1_1") (pintype "passive"))
    )
    (net (code "51") (name "Net-(1VD1-PadC)") (class "Default")
      (node (ref "1VD1") (pin "C") (pinfunction "C_C") (pintype "passive"))
      (node (ref "ISP6") (pin "2") (pinfunction "2_2") (pintype "passive"))
    )
    (net (code "52") (name "Net-(1VT1-B)") (class "Default")
      (node (ref "1R20") (pin "1") (pinfunction "1_1") (pintype "passive"))
      (node (ref "1VT1") (pin "1") (pinfunction "B_1") (pintype "passive"))
    )
    (net (code "53") (name "Net-(1VT1-C)") (class "Default")
      (node (ref "1R17") (pin "1") (pinfunction "1_1") (pintype "passive"))
      (node (ref "1VT1") (pin "3") (pinfunction "C_3") (pintype "passive"))
    )
    (net (code "54") (name "Net-(1VT1-E)") (class "Default")
      (node (ref "1VT1") (pin "2") (pinfunction "E_2") (pintype "passive"))
      (node (ref "RJ6") (pin "2") (pinfunction "2_2") (pintype "passive"))
    )
    (net (code "55") (name "Net-(1VT3-B)") (class "Default")
      (node (ref "1R16") (pin "2") (pinfunction "2_2") (pintype "passive"))
      (node (ref "1VT3") (pin "1") (pinfunction "B_1") (pintype "passive"))
    )
    (net (code "56") (name "Net-(2D1-CTS_N)") (class "Default")
      (node (ref "2D1") (pin "11") (pinfunction "CTS_N_11") (pintype "bidirectional"))
      (node (ref "JI") (pin "1") (pinfunction "1_1") (pintype "passive"))
    )
    (net (code "57") (name "Net-(2D1-DCD_N)") (class "Default")
      (node (ref "2D1") (pin "10") (pinfunction "DCD_N_10") (pintype "bidirectional"))
      (node (ref "2R8") (pin "2") (pinfunction "2_2") (pintype "passive"))
    )
    (net (code "58") (name "Net-(2D1-DM)") (class "Default")
      (node (ref "2D1") (pin "16") (pinfunction "DM_16") (pintype "bidirectional"))
      (node (ref "2R3") (pin "2") (pinfunction "2_2") (pintype "passive"))
    )
    (net (code "59") (name "Net-(2D1-DP)") (class "Default")
      (node (ref "2D1") (pin "15") (pinfunction "DP_15") (pintype "bidirectional"))
      (node (ref "2R4") (pin "2") (pinfunction "2_2") (pintype "passive"))
    )
    (net (code "60") (name "Net-(2D1-DSR_N)") (class "Default")
      (node (ref "2D1") (pin "9") (pinfunction "DSR_N_9") (pintype "bidirectional"))
      (node (ref "2R7") (pin "2") (pinfunction "2_2") (pintype "passive"))
    )
    (net (code "61") (name "Net-(2D1-DTR_N)") (class "Default")
      (node (ref "2D1") (pin "2") (pinfunction "DTR_N_2") (pintype "bidirectional"))
      (node (ref "JO") (pin "1") (pinfunction "1_1") (pintype "passive"))
    )
    (net (code "62") (name "Net-(2D1-EE_CLK)") (class "Default")
      (node (ref "2D1") (pin "13") (pinfunction "EE_CLK_13") (pintype "bidirectional"))
      (node (ref "2R9") (pin "2") (pinfunction "2_2") (pintype "passive"))
    )
    (net (code "63") (name "Net-(2D1-EE_DATA)") (class "Default")
      (node (ref "2D1") (pin "14") (pinfunction "EE_DATA_14") (pintype "bidirectional"))
      (node (ref "2R10") (pin "2") (pinfunction "2_2") (pintype "passive"))
    )
    (net (code "64") (name "Net-(2D1-GP0)") (class "Default")
      (node (ref "2D1") (pin "22") (pinfunction "GP0_22") (pintype "bidirectional"))
      (node (ref "2R2") (pin "2") (pinfunction "2_2") (pintype "passive"))
    )
    (net (code "65") (name "Net-(2D1-GP1)") (class "Default")
      (node (ref "2D1") (pin "23") (pinfunction "GP1_23") (pintype "bidirectional"))
      (node (ref "2R1") (pin "2") (pinfunction "2_2") (pintype "passive"))
    )
    (net (code "66") (name "Net-(2D1-OSC1)") (class "Default")
      (node (ref "2C2") (pin "2") (pinfunction "2_2") (pintype "passive"))
      (node (ref "2D1") (pin "27") (pinfunction "OSC1_27") (pintype "bidirectional"))
      (node (ref "2Z1") (pin "1") (pinfunction "1_1") (pintype "passive"))
    )
    (net (code "67") (name "Net-(2D1-OSC2)") (class "Default")
      (node (ref "2C1") (pin "2") (pinfunction "2_2") (pintype "passive"))
      (node (ref "2D1") (pin "28") (pinfunction "OSC2_28") (pintype "bidirectional"))
      (node (ref "2Z1") (pin "2") (pinfunction "2_2") (pintype "passive"))
    )
    (net (code "68") (name "Net-(2D1-RI_N)") (class "Default")
      (node (ref "2D1") (pin "6") (pinfunction "RI_N_6") (pintype "bidirectional"))
      (node (ref "2R6") (pin "1") (pinfunction "1_1") (pintype "passive"))
    )
    (net (code "69") (name "Net-(2D1-RTS_N)") (class "Default")
      (node (ref "2D1") (pin "3") (pinfunction "RTS_N_3") (pintype "bidirectional"))
      (node (ref "JS") (pin "1") (pinfunction "1_1") (pintype "passive"))
    )
    (net (code "70") (name "Net-(2D1-VDD_325)") (class "Default")
      (node (ref "2D1") (pin "4") (pinfunction "VDD_325_4") (pintype "bidirectional"))
      (node (ref "RJ5") (pin "1") (pinfunction "1_1") (pintype "passive"))
    )
    (net (code "71") (name "Net-(2D1-VO_33)") (class "Default")
      (node (ref "2C3") (pin "1") (pinfunction "1_1") (pintype "passive"))
      (node (ref "2D1") (pin "17") (pinfunction "VO_33_17") (pintype "bidirectional"))
      (node (ref "2R5") (pin "1") (pinfunction "1_1") (pintype "passive"))
      (node (ref "LED3V3") (pin "C") (pinfunction "C_C") (pintype "passive"))
      (node (ref "RJ5") (pin "2") (pinfunction "2_2") (pintype "passive"))
    )
    (net (code "72") (name "Net-(2R3-Pad1)") (class "Default")
      (node (ref "2R3") (pin "1") (pinfunction "1_1") (pintype "passive"))
      (node (ref "USB") (pin "2") (pinfunction "2_2") (pintype "passive"))
    )
    (net (code "73") (name "Net-(2R4-Pad1)") (class "Default")
      (node (ref "2R4") (pin "1") (pinfunction "1_1") (pintype "passive"))
      (node (ref "2R5") (pin "2") (pinfunction "2_2") (pintype "passive"))
      (node (ref "USB") (pin "3") (pinfunction "3_3") (pintype "passive"))
    )
    (net (code "74") (name "Net-(2R11-Pad1)") (class "Default")
      (node (ref "2R11") (pin "1") (pinfunction "1_1") (pintype "passive"))
      (node (ref "LED3V3") (pin "A") (pinfunction "A_A") (pintype "passive"))
    )
    (net (code "75") (name "Net-(3D1-DC)") (class "Default")
      (node (ref "3D1") (pin "8") (pinfunction "DC_8") (pintype "passive"))
      (node (ref "3R2") (pin "1") (pinfunction "1_1") (pintype "passive"))
    )
    (net (code "76") (name "Net-(3D1-FB)") (class "Default")
      (node (ref "3D1") (pin "5") (pinfunction "FB_5") (pintype "passive"))
      (node (ref "3R3") (pin "2") (pinfunction "2_2") (pintype "passive"))
      (node (ref "3R4") (pin "1") (pinfunction "1_1") (pintype "passive"))
    )
    (net (code "77") (name "Net-(3D1-SWC)") (class "Default")
      (node (ref "3D1") (pin "1") (pinfunction "SWC_1") (pintype "passive"))
      (node (ref "3L1") (pin "2") (pinfunction "2_2") (pintype "passive"))
      (node (ref "3VD1") (pin "A") (pinfunction "A_A") (pintype "passive"))
    )
    (net (code "78") (name "Net-(3D1-TC)") (class "Default")
      (node (ref "3C4") (pin "1") (pinfunction "1_1") (pintype "passive"))
      (node (ref "3D1") (pin "3") (pinfunction "TC_3") (pintype "passive"))
    )
    (net (code "79") (name "Net-(4C1-Pad2)") (class "Default")
      (node (ref "4C1") (pin "2") (pinfunction "2_2") (pintype "passive"))
      (node (ref "4R1") (pin "2") (pinfunction "2_2") (pintype "passive"))
      (node (ref "4R2") (pin "1") (pinfunction "1_1") (pintype "passive"))
    )
    (net (code "80") (name "Net-(4VT1-B)") (class "Default")
      (node (ref "4R2") (pin "2") (pinfunction "2_2") (pintype "passive"))
      (node (ref "4R3") (pin "2") (pinfunction "2_2") (pintype "passive"))
      (node (ref "4VT1") (pin "1") (pinfunction "B_1") (pintype "passive"))
    )
    (net (code "81") (name "Net-(4VT1-C)") (class "Default")
      (node (ref "4R4") (pin "2") (pinfunction "2_2") (pintype "passive"))
      (node (ref "4VT1") (pin "3") (pinfunction "C_3") (pintype "passive"))
      (node (ref "4VT2") (pin "1") (pinfunction "G_1") (pintype "passive"))
    )
    (net (code "82") (name "Net-(4VT3-G)") (class "Default")
      (node (ref "4R5") (pin "2") (pinfunction "2_2") (pintype "passive"))
      (node (ref "4VT3") (pin "1") (pinfunction "G_1") (pintype "passive"))
    )
    (net (code "83") (name "Net-(ISP6-Pad1)") (class "Default")
      (node (ref "ISP6") (pin "1") (pinfunction "1_1") (pintype "passive"))
      (node (ref "RJ2") (pin "1") (pinfunction "1_1") (pintype "passive"))
    )
    (net (code "84") (name "Net-(RJ3-Pad2)") (class "Default")
      (node (ref "RJ3") (pin "2") (pinfunction "2_2") (pintype "passive"))
      (node (ref "RJ4") (pin "1") (pinfunction "1_1") (pintype "passive"))
    )
    (net (code "85") (name "Net-(RJ7-Pad2)") (class "Default")
      (node (ref "RJ7") (pin "2") (pinfunction "2_2") (pintype "passive"))
      (node (ref "X2") (pin "RESET") (pinfunction "RESET_RESET") (pintype "bidirectional"))
    )
    (net (code "86") (name "Net-(RJ8-Pad1)") (class "Default")
      (node (ref "RJ8") (pin "1") (pinfunction "1_1") (pintype "passive"))
      (node (ref "USB") (pin "1") (pinfunction "1_1") (pintype "passive"))
    )
    (net (code "87") (name "Net-(S1-P)") (class "Default")
      (node (ref "1C2") (pin "1") (pinfunction "1_1") (pintype "passive"))
      (node (ref "1C8") (pin "1") (pinfunction "1_1") (pintype "passive"))
      (node (ref "RJ9") (pin "2") (pinfunction "2_2") (pintype "passive"))
      (node (ref "S1") (pin "3") (pinfunction "P_3") (pintype "passive"))
      (node (ref "S1") (pin "4") (pinfunction "P1_4") (pintype "passive"))
      (node (ref "U$1") (pin "P$1") (pinfunction "P$1_P$1") (pintype "bidirectional"))
    )
    (net (code "88") (name "unconnected-(1D1-(ADC0)PA0-Pad37)") (class "Default")
      (node (ref "1D1") (pin "37") (pinfunction "(ADC0)PA0_37") (pintype "bidirectional"))
    )
    (net (code "89") (name "unconnected-(1D1-(ADC1)PA1-Pad36)") (class "Default")
      (node (ref "1D1") (pin "36") (pinfunction "(ADC1)PA1_36") (pintype "bidirectional"))
    )
    (net (code "90") (name "unconnected-(1D1-(ADC2)PA2-Pad35)") (class "Default")
      (node (ref "1D1") (pin "35") (pinfunction "(ADC2)PA2_35") (pintype "bidirectional"))
    )
    (net (code "91") (name "unconnected-(1D1-(ADC3)PA3-Pad34)") (class "Default")
      (node (ref "1D1") (pin "34") (pinfunction "(ADC3)PA3_34") (pintype "bidirectional"))
    )
    (net (code "92") (name "unconnected-(1D1-(OC1B)PD4-Pad13)") (class "Default")
      (node (ref "1D1") (pin "13") (pinfunction "(OC1B)PD4_13") (pintype "bidirectional"))
    )
    (net (code "93") (name "unconnected-(1D2A-~{QH}-Pad7)") (class "Default")
      (node (ref "1D2") (pin "7") (pinfunction "~{QH}_7") (pintype "output"))
    )
    (net (code "94") (name "unconnected-(2D1-SHTD_N-Pad12)") (class "Default")
      (node (ref "2D1") (pin "12") (pinfunction "SHTD_N_12") (pintype "bidirectional"))
    )
  )
)
